# Sheet.net
KiCad netlist of a schematic drawn in Altium Designer
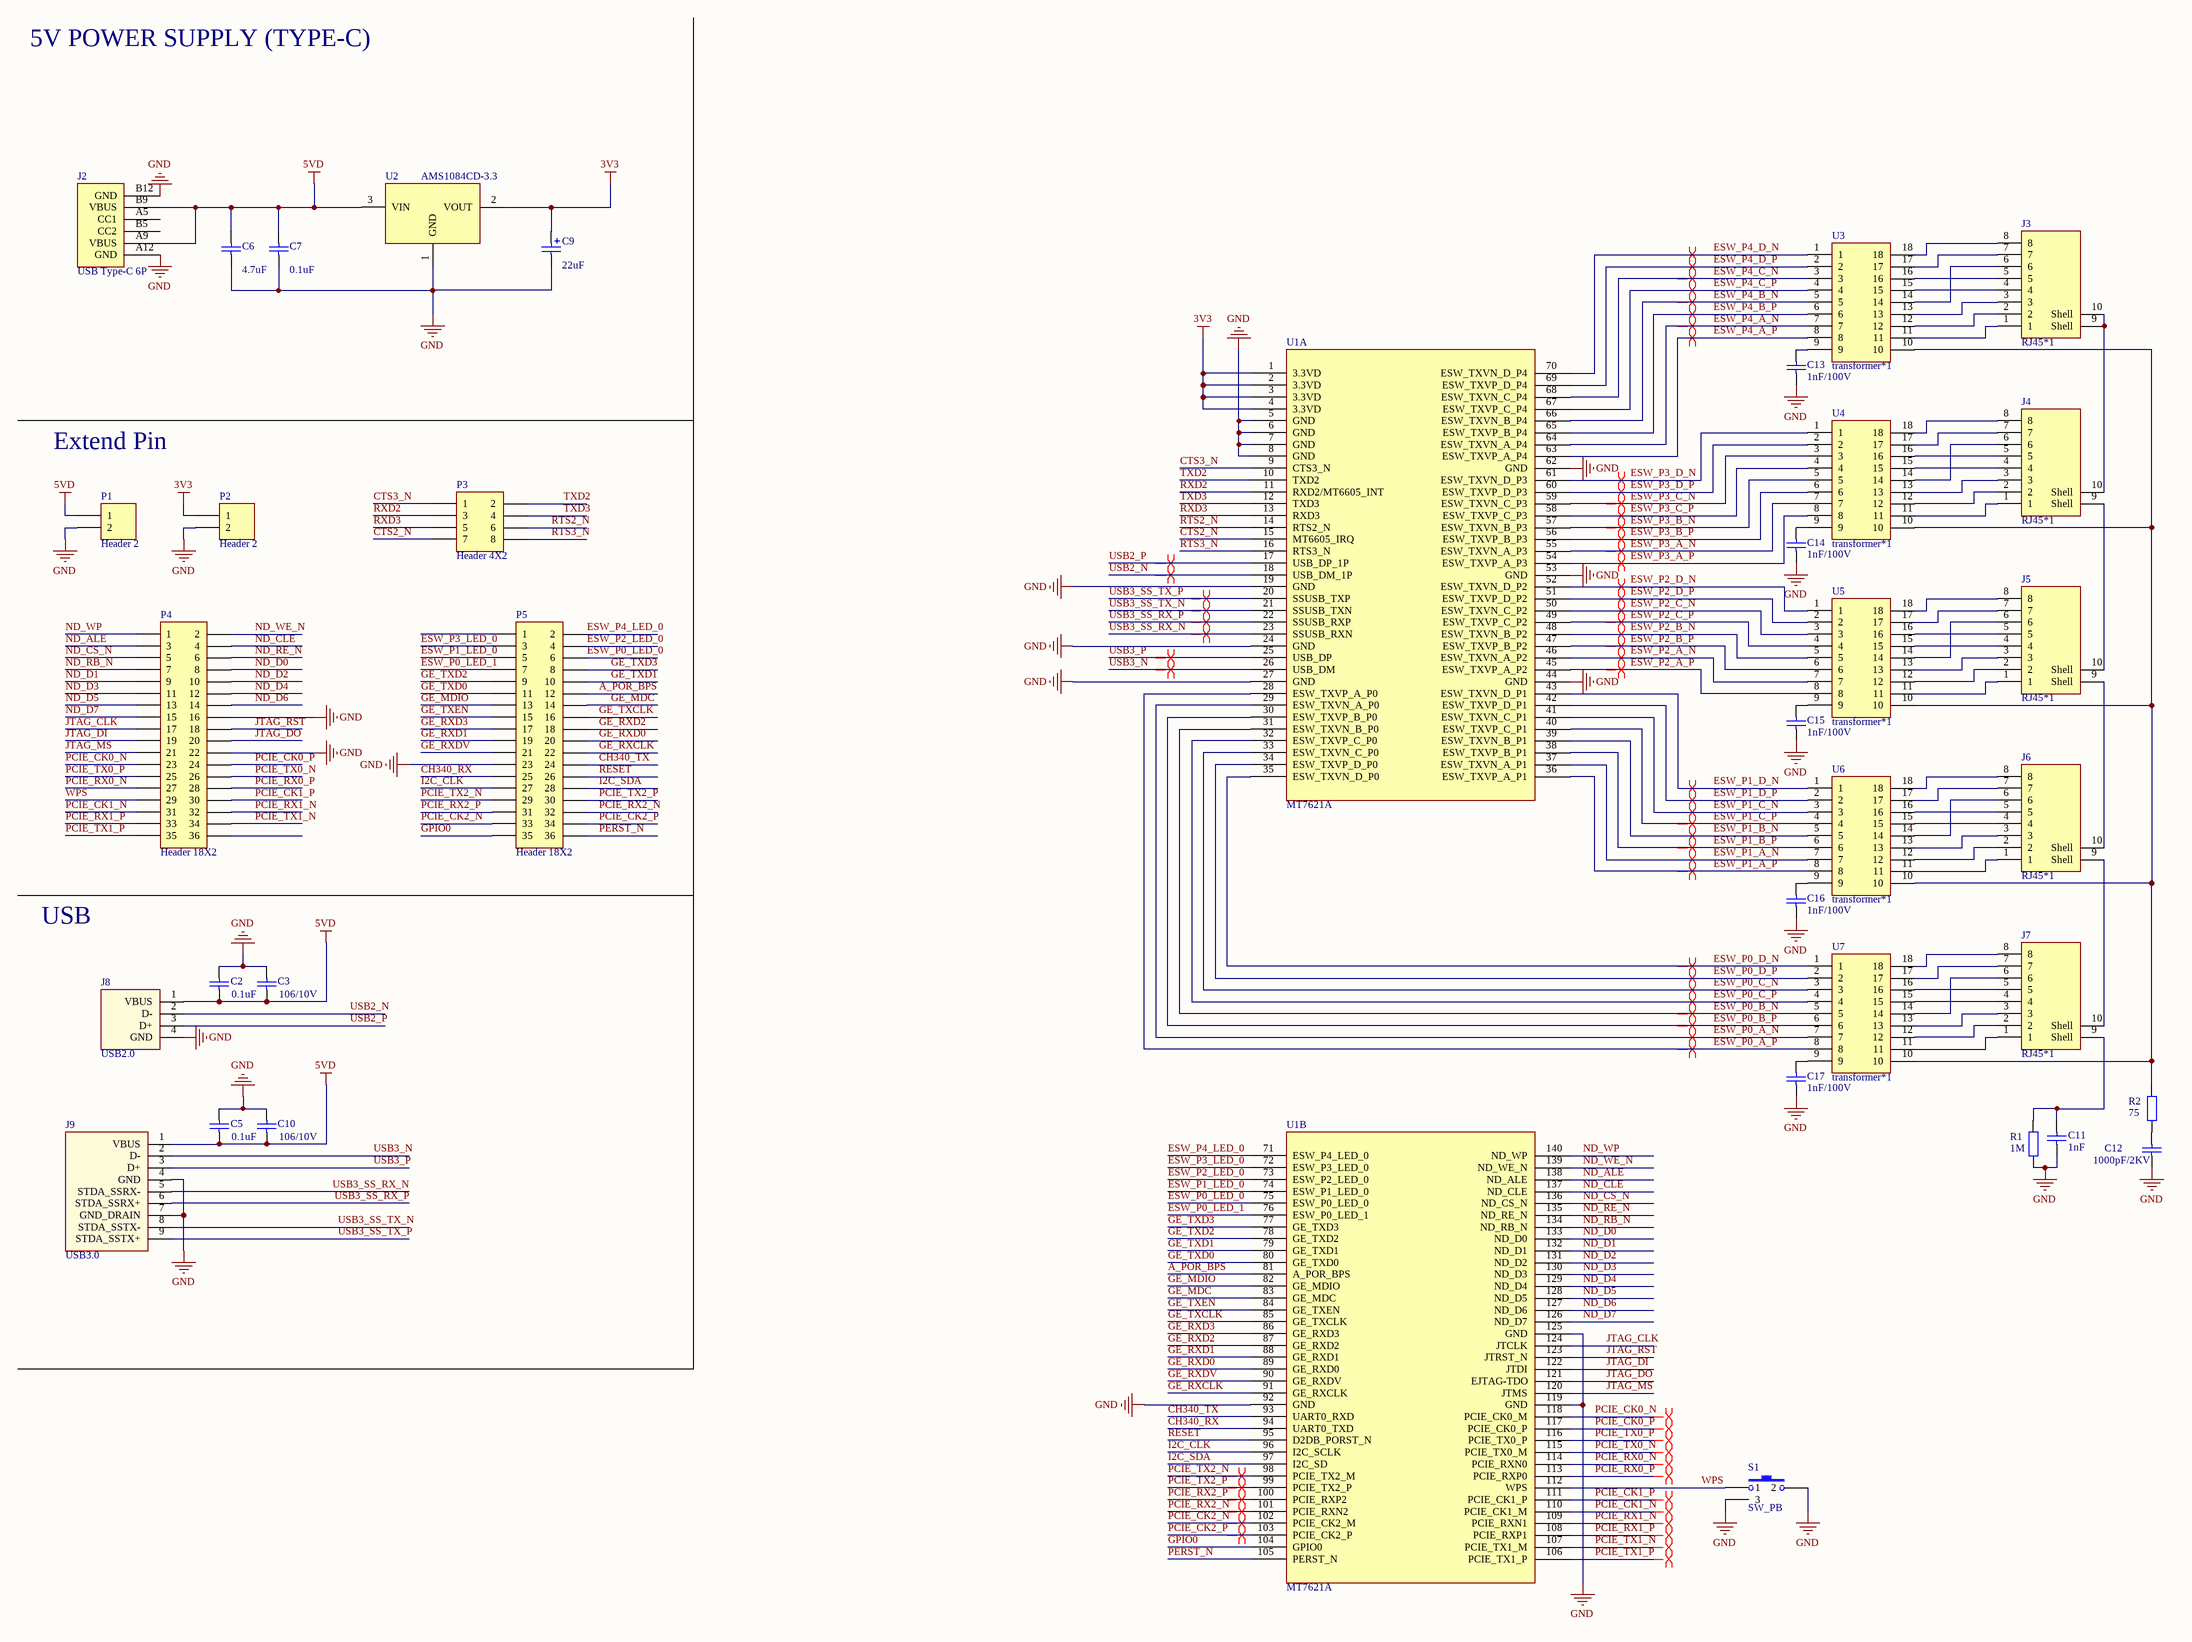
[diagram p0: Sheet.SchDoc]

(export (version "E")
  (design (tool "Eeschema 10.0.6"))
  (components
    (comp (ref "C2")
      (value "0.1uF")
      (footprint "6-0805")
      (description "Capacitor")
      (fields (field (name "Comment") "Cap") (field (name "PUBLISHER") "Altium Limited"))
      (libsource (lib "Miscellaneous Devices") (part "Cap"))
    )
    (comp (ref "C3")
      (value "106/10V")
      (footprint "6-0805")
      (description "Capacitor")
      (fields (field (name "Comment") "Cap") (field (name "PUBLISHER") "Altium Limited"))
      (libsource (lib "Miscellaneous Devices") (part "Cap"))
    )
    (comp (ref "C5")
      (value "0.1uF")
      (footprint "6-0805")
      (description "Capacitor")
      (fields (field (name "Comment") "Cap") (field (name "PUBLISHER") "Altium Limited"))
      (libsource (lib "Miscellaneous Devices") (part "Cap"))
    )
    (comp (ref "C6")
      (value "4.7uF")
      (footprint "6-0805")
      (description "Capacitor")
      (fields (field (name "Comment") "Cap") (field (name "PUBLISHER") "Altium Limited"))
      (libsource (lib "Miscellaneous Devices") (part "Cap"))
    )
    (comp (ref "C7")
      (value "0.1uF")
      (footprint "6-0805")
      (description "Capacitor")
      (fields (field (name "Comment") "Cap") (field (name "PUBLISHER") "Altium Limited"))
      (libsource (lib "Miscellaneous Devices") (part "Cap"))
    )
    (comp (ref "C9")
      (value "22uF")
      (footprint "3528B")
      (description "Polarized Capacitor (Axial)")
      (fields (field (name "Comment") "Cap Pol2") (field (name "PUBLISHER") "Altium Limited"))
      (libsource (lib "Miscellaneous Devices") (part "Cap Pol2"))
    )
    (comp (ref "C10")
      (value "106/10V")
      (footprint "6-0805")
      (description "Capacitor")
      (fields (field (name "Comment") "Cap") (field (name "PUBLISHER") "Altium Limited"))
      (libsource (lib "Miscellaneous Devices") (part "Cap"))
    )
    (comp (ref "C11")
      (value "1nF")
      (footprint "8-1206")
      (description "Capacitor")
      (fields (field (name "Comment") "Cap") (field (name "PUBLISHER") "Altium Limited"))
      (libsource (lib "Miscellaneous Devices") (part "Cap"))
    )
    (comp (ref "C12")
      (value "1000pF/2KV")
      (footprint "8-1206")
      (description "Capacitor")
      (fields (field (name "Comment") "Cap") (field (name "PUBLISHER") "Altium Limited"))
      (libsource (lib "Miscellaneous Devices") (part "Cap"))
    )
    (comp (ref "C13")
      (value "1nF/100V")
      (footprint "6-0805")
      (description "Capacitor")
      (fields (field (name "Comment") "Cap") (field (name "PUBLISHER") "Altium Limited"))
      (libsource (lib "Miscellaneous Devices") (part "Cap"))
    )
    (comp (ref "C14")
      (value "1nF/100V")
      (footprint "6-0805")
      (description "Capacitor")
      (fields (field (name "Comment") "Cap") (field (name "PUBLISHER") "Altium Limited"))
      (libsource (lib "Miscellaneous Devices") (part "Cap"))
    )
    (comp (ref "C15")
      (value "1nF/100V")
      (footprint "6-0805")
      (description "Capacitor")
      (fields (field (name "Comment") "Cap") (field (name "PUBLISHER") "Altium Limited"))
      (libsource (lib "Miscellaneous Devices") (part "Cap"))
    )
    (comp (ref "C16")
      (value "1nF/100V")
      (footprint "6-0805")
      (description "Capacitor")
      (fields (field (name "Comment") "Cap") (field (name "PUBLISHER") "Altium Limited"))
      (libsource (lib "Miscellaneous Devices") (part "Cap"))
    )
    (comp (ref "C17")
      (value "1nF/100V")
      (footprint "6-0805")
      (description "Capacitor")
      (fields (field (name "Comment") "Cap") (field (name "PUBLISHER") "Altium Limited"))
      (libsource (lib "Miscellaneous Devices") (part "Cap"))
    )
    (comp (ref "J2")
      (value "USB Type-C 6P")
      (footprint "USB Type-C 6P")
      (libsource (lib "7621_cmp") (part "USB Type-C 6P"))
    )
    (comp (ref "J3") (value "RJ45*1") (libsource (lib "7621_cmp") (part "RJ45*1")))
    (comp (ref "J4") (value "RJ45*1") (libsource (lib "7621_cmp") (part "RJ45*1")))
    (comp (ref "J5") (value "RJ45*1") (libsource (lib "7621_cmp") (part "RJ45*1")))
    (comp (ref "J6") (value "RJ45*1") (libsource (lib "7621_cmp") (part "RJ45*1")))
    (comp (ref "J7") (value "RJ45*1") (libsource (lib "7621_cmp") (part "RJ45*1")))
    (comp (ref "J8") (value "USB2.0") (footprint "USB2.0") (libsource (lib "7621_cmp") (part "USB2.0")))
    (comp (ref "J9") (value "USB3.0") (footprint "USB3.0_0") (libsource (lib "7621_cmp") (part "USB3.0")))
    (comp (ref "P1")
      (value "Header 2")
      (footprint "HDR1X2")
      (description "Header, 2-Pin")
      (fields (field (name "PUBLISHER") "Altium Limited"))
      (libsource (lib "Miscellaneous Connectors") (part "Header 2"))
    )
    (comp (ref "P2")
      (value "Header 2")
      (footprint "HDR1X2")
      (description "Header, 2-Pin")
      (fields (field (name "PUBLISHER") "Altium Limited"))
      (libsource (lib "Miscellaneous Connectors") (part "Header 2"))
    )
    (comp (ref "P3")
      (value "Header 4X2")
      (footprint "HDR2X4")
      (description "Header, 4-Pin, Dual row")
      (fields (field (name "PUBLISHER") "Altium Limited"))
      (libsource (lib "Miscellaneous Connectors") (part "Header 4X2"))
    )
    (comp (ref "P4")
      (value "Header 18X2")
      (footprint "HDR2X18")
      (description "Header, 18-Pin, Dual row")
      (fields (field (name "PUBLISHER") "Altium Limited"))
      (libsource (lib "Miscellaneous Connectors") (part "Header 18X2"))
    )
    (comp (ref "P5")
      (value "Header 18X2")
      (footprint "HDR2X18")
      (description "Header, 18-Pin, Dual row")
      (fields (field (name "PUBLISHER") "Altium Limited"))
      (libsource (lib "Miscellaneous Connectors") (part "Header 18X2"))
    )
    (comp (ref "R1")
      (value "1M")
      (footprint "8-1206")
      (description "Resistor")
      (fields (field (name "Comment") "Res2") (field (name "PUBLISHER") "Altium Limited"))
      (libsource (lib "Miscellaneous Devices") (part "Res2"))
    )
    (comp (ref "R2")
      (value "75")
      (footprint "8-1206")
      (description "Resistor")
      (fields (field (name "Comment") "Res2") (field (name "PUBLISHER") "Altium Limited"))
      (libsource (lib "Miscellaneous Devices") (part "Res2"))
    )
    (comp (ref "S1") (value "SW_PB") (footprint "SW_PB") (libsource (lib "7621_cmp") (part "SW_PB")))
    (comp (ref "U1") (value "MT7621A") (footprint "HLK-7621") (libsource (lib "7621_cmp") (part "MT7621A")))
    (comp (ref "U2")
      (value "AMS1084CD-3.3")
      (footprint "TO252")
      (libsource (lib "7621_cmp") (part "AMS1084CD-3.3"))
    )
    (comp (ref "U3")
      (value "transformer*1")
      (footprint "transformer_G1801D")
      (libsource (lib "7621_cmp") (part "transformer*1"))
    )
    (comp (ref "U4")
      (value "transformer*1")
      (footprint "transformer_G1801D")
      (libsource (lib "7621_cmp") (part "transformer*1"))
    )
    (comp (ref "U5")
      (value "transformer*1")
      (footprint "transformer_G1801D")
      (libsource (lib "7621_cmp") (part "transformer*1"))
    )
    (comp (ref "U6")
      (value "transformer*1")
      (footprint "transformer_G1801D")
      (libsource (lib "7621_cmp") (part "transformer*1"))
    )
    (comp (ref "U7")
      (value "transformer*1")
      (footprint "transformer_G1801D")
      (libsource (lib "7621_cmp") (part "transformer*1"))
    )
  )
  (nets
    (net (code "1") (name "/A_POR_BPS") (class "Default")
      (node (ref "P5") (pin "12") (pinfunction "12_12") (pintype "passive"))
      (node (ref "U1") (pin "81") (pinfunction "A_POR_BPS_81") (pintype "passive"))
    )
    (net (code "2") (name "/CH340_RX") (class "Default")
      (node (ref "P5") (pin "25") (pinfunction "25_25") (pintype "passive"))
      (node (ref "U1") (pin "94") (pinfunction "UART0_TXD_94") (pintype "passive"))
    )
    (net (code "3") (name "/CH340_TX") (class "Default")
      (node (ref "P5") (pin "24") (pinfunction "24_24") (pintype "passive"))
      (node (ref "U1") (pin "93") (pinfunction "UART0_RXD_93") (pintype "passive"))
    )
    (net (code "4") (name "/CTS2_N") (class "Default")
      (node (ref "P3") (pin "7") (pinfunction "7_7") (pintype "passive"))
      (node (ref "U1") (pin "15") (pinfunction "MT6605_IRQ_15") (pintype "passive"))
    )
    (net (code "5") (name "/CTS3_N") (class "Default")
      (node (ref "P3") (pin "1") (pinfunction "1_1") (pintype "passive"))
      (node (ref "U1") (pin "9") (pinfunction "CTS3_N_9") (pintype "passive"))
    )
    (net (code "6") (name "/ESW_P0_A_N") (class "Default")
      (node (ref "U1") (pin "29") (pinfunction "ESW_TXVN_A_P0_29") (pintype "passive"))
      (node (ref "U7") (pin "7") (pinfunction "7_7") (pintype "passive"))
    )
    (net (code "7") (name "/ESW_P0_A_P") (class "Default")
      (node (ref "U1") (pin "28") (pinfunction "ESW_TXVP_A_P0_28") (pintype "passive"))
      (node (ref "U7") (pin "8") (pinfunction "8_8") (pintype "passive"))
    )
    (net (code "8") (name "/ESW_P0_B_N") (class "Default")
      (node (ref "U1") (pin "31") (pinfunction "ESW_TXVN_B_P0_31") (pintype "passive"))
      (node (ref "U7") (pin "5") (pinfunction "5_5") (pintype "passive"))
    )
    (net (code "9") (name "/ESW_P0_B_P") (class "Default")
      (node (ref "U1") (pin "30") (pinfunction "ESW_TXVP_B_P0_30") (pintype "passive"))
      (node (ref "U7") (pin "6") (pinfunction "6_6") (pintype "passive"))
    )
    (net (code "10") (name "/ESW_P0_C_N") (class "Default")
      (node (ref "U1") (pin "33") (pinfunction "ESW_TXVN_C_P0_33") (pintype "passive"))
      (node (ref "U7") (pin "3") (pinfunction "3_3") (pintype "passive"))
    )
    (net (code "11") (name "/ESW_P0_C_P") (class "Default")
      (node (ref "U1") (pin "32") (pinfunction "ESW_TXVP_C_P0_32") (pintype "passive"))
      (node (ref "U7") (pin "4") (pinfunction "4_4") (pintype "passive"))
    )
    (net (code "12") (name "/ESW_P0_D_N") (class "Default")
      (node (ref "U1") (pin "35") (pinfunction "ESW_TXVN_D_P0_35") (pintype "passive"))
      (node (ref "U7") (pin "1") (pinfunction "1_1") (pintype "passive"))
    )
    (net (code "13") (name "/ESW_P0_D_P") (class "Default")
      (node (ref "U1") (pin "34") (pinfunction "ESW_TXVP_D_P0_34") (pintype "passive"))
      (node (ref "U7") (pin "2") (pinfunction "2_2") (pintype "passive"))
    )
    (net (code "14") (name "/ESW_P0_LED_0") (class "Default")
      (node (ref "P5") (pin "6") (pinfunction "6_6") (pintype "passive"))
      (node (ref "U1") (pin "75") (pinfunction "ESW_P0_LED_0_75") (pintype "passive"))
    )
    (net (code "15") (name "/ESW_P0_LED_1") (class "Default")
      (node (ref "P5") (pin "7") (pinfunction "7_7") (pintype "passive"))
      (node (ref "U1") (pin "76") (pinfunction "ESW_P0_LED_1_76") (pintype "passive"))
    )
    (net (code "16") (name "/ESW_P1_A_N") (class "Default")
      (node (ref "U1") (pin "37") (pinfunction "ESW_TXVN_A_P1_37") (pintype "passive"))
      (node (ref "U6") (pin "7") (pinfunction "7_7") (pintype "passive"))
    )
    (net (code "17") (name "/ESW_P1_A_P") (class "Default")
      (node (ref "U1") (pin "36") (pinfunction "ESW_TXVP_A_P1_36") (pintype "passive"))
      (node (ref "U6") (pin "8") (pinfunction "8_8") (pintype "passive"))
    )
    (net (code "18") (name "/ESW_P1_B_N") (class "Default")
      (node (ref "U1") (pin "39") (pinfunction "ESW_TXVN_B_P1_39") (pintype "passive"))
      (node (ref "U6") (pin "5") (pinfunction "5_5") (pintype "passive"))
    )
    (net (code "19") (name "/ESW_P1_B_P") (class "Default")
      (node (ref "U1") (pin "38") (pinfunction "ESW_TXVP_B_P1_38") (pintype "passive"))
      (node (ref "U6") (pin "6") (pinfunction "6_6") (pintype "passive"))
    )
    (net (code "20") (name "/ESW_P1_C_N") (class "Default")
      (node (ref "U1") (pin "41") (pinfunction "ESW_TXVN_C_P1_41") (pintype "passive"))
      (node (ref "U6") (pin "3") (pinfunction "3_3") (pintype "passive"))
    )
    (net (code "21") (name "/ESW_P1_C_P") (class "Default")
      (node (ref "U1") (pin "40") (pinfunction "ESW_TXVP_C_P1_40") (pintype "passive"))
      (node (ref "U6") (pin "4") (pinfunction "4_4") (pintype "passive"))
    )
    (net (code "22") (name "/ESW_P1_D_N") (class "Default")
      (node (ref "U1") (pin "43") (pinfunction "ESW_TXVN_D_P1_43") (pintype "passive"))
      (node (ref "U6") (pin "1") (pinfunction "1_1") (pintype "passive"))
    )
    (net (code "23") (name "/ESW_P1_D_P") (class "Default")
      (node (ref "U1") (pin "42") (pinfunction "ESW_TXVP_D_P1_42") (pintype "passive"))
      (node (ref "U6") (pin "2") (pinfunction "2_2") (pintype "passive"))
    )
    (net (code "24") (name "/ESW_P1_LED_0") (class "Default")
      (node (ref "P5") (pin "5") (pinfunction "5_5") (pintype "passive"))
      (node (ref "U1") (pin "74") (pinfunction "ESW_P1_LED_0_74") (pintype "passive"))
    )
    (net (code "25") (name "/ESW_P2_A_N") (class "Default")
      (node (ref "U1") (pin "46") (pinfunction "ESW_TXVN_A_P2_46") (pintype "passive"))
      (node (ref "U5") (pin "7") (pinfunction "7_7") (pintype "passive"))
    )
    (net (code "26") (name "/ESW_P2_A_P") (class "Default")
      (node (ref "U1") (pin "45") (pinfunction "ESW_TXVP_A_P2_45") (pintype "passive"))
      (node (ref "U5") (pin "8") (pinfunction "8_8") (pintype "passive"))
    )
    (net (code "27") (name "/ESW_P2_B_N") (class "Default")
      (node (ref "U1") (pin "48") (pinfunction "ESW_TXVN_B_P2_48") (pintype "passive"))
      (node (ref "U5") (pin "5") (pinfunction "5_5") (pintype "passive"))
    )
    (net (code "28") (name "/ESW_P2_B_P") (class "Default")
      (node (ref "U1") (pin "47") (pinfunction "ESW_TXVP_B_P2_47") (pintype "passive"))
      (node (ref "U5") (pin "6") (pinfunction "6_6") (pintype "passive"))
    )
    (net (code "29") (name "/ESW_P2_C_N") (class "Default")
      (node (ref "U1") (pin "50") (pinfunction "ESW_TXVN_C_P2_50") (pintype "passive"))
      (node (ref "U5") (pin "3") (pinfunction "3_3") (pintype "passive"))
    )
    (net (code "30") (name "/ESW_P2_C_P") (class "Default")
      (node (ref "U1") (pin "49") (pinfunction "ESW_TXVP_C_P2_49") (pintype "passive"))
      (node (ref "U5") (pin "4") (pinfunction "4_4") (pintype "passive"))
    )
    (net (code "31") (name "/ESW_P2_D_N") (class "Default")
      (node (ref "U1") (pin "52") (pinfunction "ESW_TXVN_D_P2_52") (pintype "passive"))
      (node (ref "U5") (pin "1") (pinfunction "1_1") (pintype "passive"))
    )
    (net (code "32") (name "/ESW_P2_D_P") (class "Default")
      (node (ref "U1") (pin "51") (pinfunction "ESW_TXVP_D_P2_51") (pintype "passive"))
      (node (ref "U5") (pin "2") (pinfunction "2_2") (pintype "passive"))
    )
    (net (code "33") (name "/ESW_P2_LED_0") (class "Default")
      (node (ref "P5") (pin "4") (pinfunction "4_4") (pintype "passive"))
      (node (ref "U1") (pin "73") (pinfunction "ESW_P2_LED_0_73") (pintype "passive"))
    )
    (net (code "34") (name "/ESW_P3_A_N") (class "Default")
      (node (ref "U1") (pin "55") (pinfunction "ESW_TXVN_A_P3_55") (pintype "passive"))
      (node (ref "U4") (pin "7") (pinfunction "7_7") (pintype "passive"))
    )
    (net (code "35") (name "/ESW_P3_A_P") (class "Default")
      (node (ref "U1") (pin "54") (pinfunction "ESW_TXVP_A_P3_54") (pintype "passive"))
      (node (ref "U4") (pin "8") (pinfunction "8_8") (pintype "passive"))
    )
    (net (code "36") (name "/ESW_P3_B_N") (class "Default")
      (node (ref "U1") (pin "57") (pinfunction "ESW_TXVN_B_P3_57") (pintype "passive"))
      (node (ref "U4") (pin "5") (pinfunction "5_5") (pintype "passive"))
    )
    (net (code "37") (name "/ESW_P3_B_P") (class "Default")
      (node (ref "U1") (pin "56") (pinfunction "ESW_TXVP_B_P3_56") (pintype "passive"))
      (node (ref "U4") (pin "6") (pinfunction "6_6") (pintype "passive"))
    )
    (net (code "38") (name "/ESW_P3_C_N") (class "Default")
      (node (ref "U1") (pin "59") (pinfunction "ESW_TXVN_C_P3_59") (pintype "passive"))
      (node (ref "U4") (pin "3") (pinfunction "3_3") (pintype "passive"))
    )
    (net (code "39") (name "/ESW_P3_C_P") (class "Default")
      (node (ref "U1") (pin "58") (pinfunction "ESW_TXVP_C_P3_58") (pintype "passive"))
      (node (ref "U4") (pin "4") (pinfunction "4_4") (pintype "passive"))
    )
    (net (code "40") (name "/ESW_P3_D_N") (class "Default")
      (node (ref "U1") (pin "61") (pinfunction "ESW_TXVN_D_P3_61") (pintype "passive"))
      (node (ref "U4") (pin "1") (pinfunction "1_1") (pintype "passive"))
    )
    (net (code "41") (name "/ESW_P3_D_P") (class "Default")
      (node (ref "U1") (pin "60") (pinfunction "ESW_TXVP_D_P3_60") (pintype "passive"))
      (node (ref "U4") (pin "2") (pinfunction "2_2") (pintype "passive"))
    )
    (net (code "42") (name "/ESW_P3_LED_0") (class "Default")
      (node (ref "P5") (pin "3") (pinfunction "3_3") (pintype "passive"))
      (node (ref "U1") (pin "72") (pinfunction "ESW_P3_LED_0_72") (pintype "passive"))
    )
    (net (code "43") (name "/ESW_P4_A_N") (class "Default")
      (node (ref "U1") (pin "64") (pinfunction "ESW_TXVN_A_P4_64") (pintype "passive"))
      (node (ref "U3") (pin "7") (pinfunction "7_7") (pintype "passive"))
    )
    (net (code "44") (name "/ESW_P4_A_P") (class "Default")
      (node (ref "U1") (pin "63") (pinfunction "ESW_TXVP_A_P4_63") (pintype "passive"))
      (node (ref "U3") (pin "8") (pinfunction "8_8") (pintype "passive"))
    )
    (net (code "45") (name "/ESW_P4_B_N") (class "Default")
      (node (ref "U1") (pin "66") (pinfunction "ESW_TXVN_B_P4_66") (pintype "passive"))
      (node (ref "U3") (pin "5") (pinfunction "5_5") (pintype "passive"))
    )
    (net (code "46") (name "/ESW_P4_B_P") (class "Default")
      (node (ref "U1") (pin "65") (pinfunction "ESW_TXVP_B_P4_65") (pintype "passive"))
      (node (ref "U3") (pin "6") (pinfunction "6_6") (pintype "passive"))
    )
    (net (code "47") (name "/ESW_P4_C_N") (class "Default")
      (node (ref "U1") (pin "68") (pinfunction "ESW_TXVN_C_P4_68") (pintype "passive"))
      (node (ref "U3") (pin "3") (pinfunction "3_3") (pintype "passive"))
    )
    (net (code "48") (name "/ESW_P4_C_P") (class "Default")
      (node (ref "U1") (pin "67") (pinfunction "ESW_TXVP_C_P4_67") (pintype "passive"))
      (node (ref "U3") (pin "4") (pinfunction "4_4") (pintype "passive"))
    )
    (net (code "49") (name "/ESW_P4_D_N") (class "Default")
      (node (ref "U1") (pin "70") (pinfunction "ESW_TXVN_D_P4_70") (pintype "passive"))
      (node (ref "U3") (pin "1") (pinfunction "1_1") (pintype "passive"))
    )
    (net (code "50") (name "/ESW_P4_D_P") (class "Default")
      (node (ref "U1") (pin "69") (pinfunction "ESW_TXVP_D_P4_69") (pintype "passive"))
      (node (ref "U3") (pin "2") (pinfunction "2_2") (pintype "passive"))
    )
    (net (code "51") (name "/ESW_P4_LED_0") (class "Default")
      (node (ref "P5") (pin "2") (pinfunction "2_2") (pintype "passive"))
      (node (ref "U1") (pin "71") (pinfunction "ESW_P4_LED_0_71") (pintype "passive"))
    )
    (net (code "52") (name "/GE_MDC") (class "Default")
      (node (ref "P5") (pin "14") (pinfunction "14_14") (pintype "passive"))
      (node (ref "U1") (pin "83") (pinfunction "GE_MDC_83") (pintype "passive"))
    )
    (net (code "53") (name "/GE_MDIO") (class "Default")
      (node (ref "P5") (pin "13") (pinfunction "13_13") (pintype "passive"))
      (node (ref "U1") (pin "82") (pinfunction "GE_MDIO_82") (pintype "passive"))
    )
    (net (code "54") (name "/GE_RXCLK") (class "Default")
      (node (ref "P5") (pin "22") (pinfunction "22_22") (pintype "passive"))
      (node (ref "U1") (pin "91") (pinfunction "GE_RXCLK_91") (pintype "passive"))
    )
    (net (code "55") (name "/GE_RXD0") (class "Default")
      (node (ref "P5") (pin "20") (pinfunction "20_20") (pintype "passive"))
      (node (ref "U1") (pin "89") (pinfunction "GE_RXD0_89") (pintype "passive"))
    )
    (net (code "56") (name "/GE_RXD1") (class "Default")
      (node (ref "P5") (pin "19") (pinfunction "19_19") (pintype "passive"))
      (node (ref "U1") (pin "88") (pinfunction "GE_RXD1_88") (pintype "passive"))
    )
    (net (code "57") (name "/GE_RXD2") (class "Default")
      (node (ref "P5") (pin "18") (pinfunction "18_18") (pintype "passive"))
      (node (ref "U1") (pin "87") (pinfunction "GE_RXD2_87") (pintype "passive"))
    )
    (net (code "58") (name "/GE_RXD3") (class "Default")
      (node (ref "P5") (pin "17") (pinfunction "17_17") (pintype "passive"))
      (node (ref "U1") (pin "86") (pinfunction "GE_RXD3_86") (pintype "passive"))
    )
    (net (code "59") (name "/GE_RXDV") (class "Default")
      (node (ref "P5") (pin "21") (pinfunction "21_21") (pintype "passive"))
      (node (ref "U1") (pin "90") (pinfunction "GE_RXDV_90") (pintype "passive"))
    )
    (net (code "60") (name "/GE_TXCLK") (class "Default")
      (node (ref "P5") (pin "16") (pinfunction "16_16") (pintype "passive"))
      (node (ref "U1") (pin "85") (pinfunction "GE_TXCLK_85") (pintype "passive"))
    )
    (net (code "61") (name "/GE_TXD0") (class "Default")
      (node (ref "P5") (pin "11") (pinfunction "11_11") (pintype "passive"))
      (node (ref "U1") (pin "80") (pinfunction "GE_TXD0_80") (pintype "passive"))
    )
    (net (code "62") (name "/GE_TXD1") (class "Default")
      (node (ref "P5") (pin "10") (pinfunction "10_10") (pintype "passive"))
      (node (ref "U1") (pin "79") (pinfunction "GE_TXD1_79") (pintype "passive"))
    )
    (net (code "63") (name "/GE_TXD2") (class "Default")
      (node (ref "P5") (pin "9") (pinfunction "9_9") (pintype "passive"))
      (node (ref "U1") (pin "78") (pinfunction "GE_TXD2_78") (pintype "passive"))
    )
    (net (code "64") (name "/GE_TXD3") (class "Default")
      (node (ref "P5") (pin "8") (pinfunction "8_8") (pintype "passive"))
      (node (ref "U1") (pin "77") (pinfunction "GE_TXD3_77") (pintype "passive"))
    )
    (net (code "65") (name "/GE_TXEN") (class "Default")
      (node (ref "P5") (pin "15") (pinfunction "15_15") (pintype "passive"))
      (node (ref "U1") (pin "84") (pinfunction "GE_TXEN_84") (pintype "passive"))
    )
    (net (code "66") (name "/GPIO0") (class "Default")
      (node (ref "P5") (pin "35") (pinfunction "35_35") (pintype "passive"))
      (node (ref "U1") (pin "104") (pinfunction "GPIO0_104") (pintype "passive"))
    )
    (net (code "67") (name "/I2C_CLK") (class "Default")
      (node (ref "P5") (pin "27") (pinfunction "27_27") (pintype "passive"))
      (node (ref "U1") (pin "96") (pinfunction "I2C_SCLK_96") (pintype "passive"))
    )
    (net (code "68") (name "/I2C_SDA") (class "Default")
      (node (ref "P5") (pin "28") (pinfunction "28_28") (pintype "passive"))
      (node (ref "U1") (pin "97") (pinfunction "I2C_SD_97") (pintype "passive"))
    )
    (net (code "69") (name "/JTAG_CLK") (class "Default")
      (node (ref "P4") (pin "17") (pinfunction "17_17") (pintype "passive"))
      (node (ref "U1") (pin "124") (pinfunction "JTCLK_124") (pintype "passive"))
    )
    (net (code "70") (name "/JTAG_DI") (class "Default")
      (node (ref "P4") (pin "19") (pinfunction "19_19") (pintype "passive"))
      (node (ref "U1") (pin "122") (pinfunction "JTDI_122") (pintype "passive"))
    )
    (net (code "71") (name "/JTAG_DO") (class "Default")
      (node (ref "P4") (pin "20") (pinfunction "20_20") (pintype "passive"))
      (node (ref "U1") (pin "121") (pinfunction "EJTAG-TDO_121") (pintype "passive"))
    )
    (net (code "72") (name "/JTAG_MS") (class "Default")
      (node (ref "P4") (pin "21") (pinfunction "21_21") (pintype "passive"))
      (node (ref "U1") (pin "120") (pinfunction "JTMS_120") (pintype "passive"))
    )
    (net (code "73") (name "/JTAG_RST") (class "Default")
      (node (ref "P4") (pin "18") (pinfunction "18_18") (pintype "passive"))
      (node (ref "U1") (pin "123") (pinfunction "JTRST_N_123") (pintype "passive"))
    )
    (net (code "74") (name "/ND_ALE") (class "Default")
      (node (ref "P4") (pin "3") (pinfunction "3_3") (pintype "passive"))
      (node (ref "U1") (pin "138") (pinfunction "ND_ALE_138") (pintype "passive"))
    )
    (net (code "75") (name "/ND_CLE") (class "Default")
      (node (ref "P4") (pin "4") (pinfunction "4_4") (pintype "passive"))
      (node (ref "U1") (pin "137") (pinfunction "ND_CLE_137") (pintype "passive"))
    )
    (net (code "76") (name "/ND_CS_N") (class "Default")
      (node (ref "P4") (pin "5") (pinfunction "5_5") (pintype "passive"))
      (node (ref "U1") (pin "136") (pinfunction "ND_CS_N_136") (pintype "passive"))
    )
    (net (code "77") (name "/ND_D0") (class "Default")
      (node (ref "P4") (pin "8") (pinfunction "8_8") (pintype "passive"))
      (node (ref "U1") (pin "133") (pinfunction "ND_D0_133") (pintype "passive"))
    )
    (net (code "78") (name "/ND_D1") (class "Default")
      (node (ref "P4") (pin "9") (pinfunction "9_9") (pintype "passive"))
      (node (ref "U1") (pin "132") (pinfunction "ND_D1_132") (pintype "passive"))
    )
    (net (code "79") (name "/ND_D2") (class "Default")
      (node (ref "P4") (pin "10") (pinfunction "10_10") (pintype "passive"))
      (node (ref "U1") (pin "131") (pinfunction "ND_D2_131") (pintype "passive"))
    )
    (net (code "80") (name "/ND_D3") (class "Default")
      (node (ref "P4") (pin "11") (pinfunction "11_11") (pintype "passive"))
      (node (ref "U1") (pin "130") (pinfunction "ND_D3_130") (pintype "passive"))
    )
    (net (code "81") (name "/ND_D4") (class "Default")
      (node (ref "P4") (pin "12") (pinfunction "12_12") (pintype "passive"))
      (node (ref "U1") (pin "129") (pinfunction "ND_D4_129") (pintype "passive"))
    )
    (net (code "82") (name "/ND_D5") (class "Default")
      (node (ref "P4") (pin "13") (pinfunction "13_13") (pintype "passive"))
      (node (ref "U1") (pin "128") (pinfunction "ND_D5_128") (pintype "passive"))
    )
    (net (code "83") (name "/ND_D6") (class "Default")
      (node (ref "P4") (pin "14") (pinfunction "14_14") (pintype "passive"))
      (node (ref "U1") (pin "127") (pinfunction "ND_D6_127") (pintype "passive"))
    )
    (net (code "84") (name "/ND_D7") (class "Default")
      (node (ref "P4") (pin "15") (pinfunction "15_15") (pintype "passive"))
      (node (ref "U1") (pin "126") (pinfunction "ND_D7_126") (pintype "passive"))
    )
    (net (code "85") (name "/ND_RB_N") (class "Default")
      (node (ref "P4") (pin "7") (pinfunction "7_7") (pintype "passive"))
      (node (ref "U1") (pin "134") (pinfunction "ND_RB_N_134") (pintype "passive"))
    )
    (net (code "86") (name "/ND_RE_N") (class "Default")
      (node (ref "P4") (pin "6") (pinfunction "6_6") (pintype "passive"))
      (node (ref "U1") (pin "135") (pinfunction "ND_RE_N_135") (pintype "passive"))
    )
    (net (code "87") (name "/ND_WE_N") (class "Default")
      (node (ref "P4") (pin "2") (pinfunction "2_2") (pintype "passive"))
      (node (ref "U1") (pin "139") (pinfunction "ND_WE_N_139") (pintype "passive"))
    )
    (net (code "88") (name "/ND_WP") (class "Default")
      (node (ref "P4") (pin "1") (pinfunction "1_1") (pintype "passive"))
      (node (ref "U1") (pin "140") (pinfunction "ND_WP_140") (pintype "passive"))
    )
    (net (code "89") (name "/PCIE_CK0_N") (class "Default")
      (node (ref "P4") (pin "23") (pinfunction "23_23") (pintype "passive"))
      (node (ref "U1") (pin "118") (pinfunction "PCIE_CK0_M_118") (pintype "passive"))
    )
    (net (code "90") (name "/PCIE_CK0_P") (class "Default")
      (node (ref "P4") (pin "24") (pinfunction "24_24") (pintype "passive"))
      (node (ref "U1") (pin "117") (pinfunction "PCIE_CK0_P_117") (pintype "passive"))
    )
    (net (code "91") (name "/PCIE_CK1_N") (class "Default")
      (node (ref "P4") (pin "31") (pinfunction "31_31") (pintype "passive"))
      (node (ref "U1") (pin "110") (pinfunction "PCIE_CK1_M_110") (pintype "passive"))
    )
    (net (code "92") (name "/PCIE_CK1_P") (class "Default")
      (node (ref "P4") (pin "30") (pinfunction "30_30") (pintype "passive"))
      (node (ref "U1") (pin "111") (pinfunction "PCIE_CK1_P_111") (pintype "passive"))
    )
    (net (code "93") (name "/PCIE_CK2_N") (class "Default")
      (node (ref "P5") (pin "33") (pinfunction "33_33") (pintype "passive"))
      (node (ref "U1") (pin "102") (pinfunction "PCIE_CK2_M_102") (pintype "passive"))
    )
    (net (code "94") (name "/PCIE_CK2_P") (class "Default")
      (node (ref "P5") (pin "34") (pinfunction "34_34") (pintype "passive"))
      (node (ref "U1") (pin "103") (pinfunction "PCIE_CK2_P_103") (pintype "passive"))
    )
    (net (code "95") (name "/PCIE_RX0_N") (class "Default")
      (node (ref "P4") (pin "27") (pinfunction "27_27") (pintype "passive"))
      (node (ref "U1") (pin "114") (pinfunction "PCIE_RXN0_114") (pintype "passive"))
    )
    (net (code "96") (name "/PCIE_RX0_P") (class "Default")
      (node (ref "P4") (pin "28") (pinfunction "28_28") (pintype "passive"))
      (node (ref "U1") (pin "113") (pinfunction "PCIE_RXP0_113") (pintype "passive"))
    )
    (net (code "97") (name "/PCIE_RX1_N") (class "Default")
      (node (ref "P4") (pin "32") (pinfunction "32_32") (pintype "passive"))
      (node (ref "U1") (pin "109") (pinfunction "PCIE_RXN1_109") (pintype "passive"))
    )
    (net (code "98") (name "/PCIE_RX1_P") (class "Default")
      (node (ref "P4") (pin "33") (pinfunction "33_33") (pintype "passive"))
      (node (ref "U1") (pin "108") (pinfunction "PCIE_RXP1_108") (pintype "passive"))
    )
    (net (code "99") (name "/PCIE_RX2_N") (class "Default")
      (node (ref "P5") (pin "32") (pinfunction "32_32") (pintype "passive"))
      (node (ref "U1") (pin "101") (pinfunction "PCIE_RXN2_101") (pintype "passive"))
    )
    (net (code "100") (name "/PCIE_RX2_P") (class "Default")
      (node (ref "P5") (pin "31") (pinfunction "31_31") (pintype "passive"))
      (node (ref "U1") (pin "100") (pinfunction "PCIE_RXP2_100") (pintype "passive"))
    )
    (net (code "101") (name "/PCIE_TX0_N") (class "Default")
      (node (ref "P4") (pin "26") (pinfunction "26_26") (pintype "passive"))
      (node (ref "U1") (pin "115") (pinfunction "PCIE_TX0_M_115") (pintype "passive"))
    )
    (net (code "102") (name "/PCIE_TX0_P") (class "Default")
      (node (ref "P4") (pin "25") (pinfunction "25_25") (pintype "passive"))
      (node (ref "U1") (pin "116") (pinfunction "PCIE_TX0_P_116") (pintype "passive"))
    )
    (net (code "103") (name "/PCIE_TX1_N") (class "Default")
      (node (ref "P4") (pin "34") (pinfunction "34_34") (pintype "passive"))
      (node (ref "U1") (pin "107") (pinfunction "PCIE_TX1_M_107") (pintype "passive"))
    )
    (net (code "104") (name "/PCIE_TX1_P") (class "Default")
      (node (ref "P4") (pin "35") (pinfunction "35_35") (pintype "passive"))
      (node (ref "U1") (pin "106") (pinfunction "PCIE_TX1_P_106") (pintype "passive"))
    )
    (net (code "105") (name "/PCIE_TX2_N") (class "Default")
      (node (ref "P5") (pin "29") (pinfunction "29_29") (pintype "passive"))
      (node (ref "U1") (pin "98") (pinfunction "PCIE_TX2_M_98") (pintype "passive"))
    )
    (net (code "106") (name "/PCIE_TX2_P") (class "Default")
      (node (ref "P5") (pin "30") (pinfunction "30_30") (pintype "passive"))
      (node (ref "U1") (pin "99") (pinfunction "PCIE_TX2_P_99") (pintype "passive"))
    )
    (net (code "107") (name "/PERST_N") (class "Default")
      (node (ref "P5") (pin "36") (pinfunction "36_36") (pintype "passive"))
      (node (ref "U1") (pin "105") (pinfunction "PERST_N_105") (pintype "passive"))
    )
    (net (code "108") (name "/RESET") (class "Default")
      (node (ref "P5") (pin "26") (pinfunction "26_26") (pintype "passive"))
      (node (ref "U1") (pin "95") (pinfunction "D2DB_PORST_N_95") (pintype "passive"))
    )
    (net (code "109") (name "/RTS2_N") (class "Default")
      (node (ref "P3") (pin "6") (pinfunction "6_6") (pintype "passive"))
      (node (ref "U1") (pin "14") (pinfunction "RTS2_N_14") (pintype "passive"))
    )
    (net (code "110") (name "/RTS3_N") (class "Default")
      (node (ref "P3") (pin "8") (pinfunction "8_8") (pintype "passive"))
      (node (ref "U1") (pin "16") (pinfunction "RTS3_N_16") (pintype "passive"))
    )
    (net (code "111") (name "/RXD2") (class "Default")
      (node (ref "P3") (pin "3") (pinfunction "3_3") (pintype "passive"))
      (node (ref "U1") (pin "11") (pinfunction "RXD2/MT6605_INT_11") (pintype "passive"))
    )
    (net (code "112") (name "/RXD3") (class "Default")
      (node (ref "P3") (pin "5") (pinfunction "5_5") (pintype "passive"))
      (node (ref "U1") (pin "13") (pinfunction "RXD3_13") (pintype "passive"))
    )
    (net (code "113") (name "/TXD2") (class "Default")
      (node (ref "P3") (pin "2") (pinfunction "2_2") (pintype "passive"))
      (node (ref "U1") (pin "10") (pinfunction "TXD2_10") (pintype "passive"))
    )
    (net (code "114") (name "/TXD3") (class "Default")
      (node (ref "P3") (pin "4") (pinfunction "4_4") (pintype "passive"))
      (node (ref "U1") (pin "12") (pinfunction "TXD3_12") (pintype "passive"))
    )
    (net (code "115") (name "/USB2_N") (class "Default")
      (node (ref "J8") (pin "2") (pinfunction "D-_2") (pintype "passive"))
      (node (ref "U1") (pin "18") (pinfunction "USB_DM_1P_18") (pintype "passive"))
    )
    (net (code "116") (name "/USB2_P") (class "Default")
      (node (ref "J8") (pin "3") (pinfunction "D+_3") (pintype "passive"))
      (node (ref "U1") (pin "17") (pinfunction "USB_DP_1P_17") (pintype "passive"))
    )
    (net (code "117") (name "/USB3_N") (class "Default")
      (node (ref "J9") (pin "2") (pinfunction "D-_2") (pintype "passive"))
      (node (ref "U1") (pin "26") (pinfunction "USB_DM_26") (pintype "passive"))
    )
    (net (code "118") (name "/USB3_P") (class "Default")
      (node (ref "J9") (pin "3") (pinfunction "D+_3") (pintype "passive"))
      (node (ref "U1") (pin "25") (pinfunction "USB_DP_25") (pintype "passive"))
    )
    (net (code "119") (name "/USB3_SS_RX_N") (class "Default")
      (node (ref "J9") (pin "5") (pinfunction "STDA_SSRX-_5") (pintype "passive"))
      (node (ref "U1") (pin "23") (pinfunction "SSUSB_RXN_23") (pintype "passive"))
    )
    (net (code "120") (name "/USB3_SS_RX_P") (class "Default")
      (node (ref "J9") (pin "6") (pinfunction "STDA_SSRX+_6") (pintype "passive"))
      (node (ref "U1") (pin "22") (pinfunction "SSUSB_RXP_22") (pintype "passive"))
    )
    (net (code "121") (name "/USB3_SS_TX_N") (class "Default")
      (node (ref "J9") (pin "8") (pinfunction "STDA_SSTX-_8") (pintype "passive"))
      (node (ref "U1") (pin "21") (pinfunction "SSUSB_TXN_21") (pintype "passive"))
    )
    (net (code "122") (name "/USB3_SS_TX_P") (class "Default")
      (node (ref "J9") (pin "9") (pinfunction "STDA_SSTX+_9") (pintype "passive"))
      (node (ref "U1") (pin "20") (pinfunction "SSUSB_TXP_20") (pintype "passive"))
    )
    (net (code "123") (name "/WPS") (class "Default")
      (node (ref "P4") (pin "29") (pinfunction "29_29") (pintype "passive"))
      (node (ref "S1") (pin "1") (pinfunction "1_1") (pintype "passive"))
      (node (ref "U1") (pin "112") (pinfunction "WPS_112") (pintype "passive"))
    )
    (net (code "124") (name "3V3") (class "Default")
      (node (ref "C9") (pin "1") (pinfunction "1_1") (pintype "passive"))
      (node (ref "P2") (pin "1") (pinfunction "1_1") (pintype "passive"))
      (node (ref "U1") (pin "1") (pinfunction "3.3VD_1") (pintype "passive"))
      (node (ref "U1") (pin "2") (pinfunction "3.3VD_2") (pintype "passive"))
      (node (ref "U1") (pin "3") (pinfunction "3.3VD_3") (pintype "passive"))
      (node (ref "U1") (pin "4") (pinfunction "3.3VD_4") (pintype "passive"))
      (node (ref "U2") (pin "2") (pinfunction "VOUT_2") (pintype "passive"))
    )
    (net (code "125") (name "5VD") (class "Default")
      (node (ref "C10") (pin "1") (pinfunction "1_1") (pintype "passive"))
      (node (ref "C2") (pin "1") (pinfunction "1_1") (pintype "passive"))
      (node (ref "C3") (pin "1") (pinfunction "1_1") (pintype "passive"))
      (node (ref "C5") (pin "1") (pinfunction "1_1") (pintype "passive"))
      (node (ref "C6") (pin "2") (pinfunction "2_2") (pintype "passive"))
      (node (ref "C7") (pin "2") (pinfunction "2_2") (pintype "passive"))
      (node (ref "J2") (pin "A9") (pinfunction "VBUS_A9") (pintype "passive"))
      (node (ref "J2") (pin "B9") (pinfunction "VBUS_B9") (pintype "passive"))
      (node (ref "J8") (pin "1") (pinfunction "VBUS_1") (pintype "passive"))
      (node (ref "J9") (pin "1") (pinfunction "VBUS_1") (pintype "passive"))
      (node (ref "P1") (pin "1") (pinfunction "1_1") (pintype "passive"))
      (node (ref "U2") (pin "3") (pinfunction "VIN_3") (pintype "passive"))
    )
    (net (code "126") (name "GND") (class "Default")
      (node (ref "C10") (pin "2") (pinfunction "2_2") (pintype "passive"))
      (node (ref "C11") (pin "1") (pinfunction "1_1") (pintype "passive"))
      (node (ref "C12") (pin "2") (pinfunction "2_2") (pintype "passive"))
      (node (ref "C13") (pin "2") (pinfunction "2_2") (pintype "passive"))
      (node (ref "C14") (pin "2") (pinfunction "2_2") (pintype "passive"))
      (node (ref "C15") (pin "2") (pinfunction "2_2") (pintype "passive"))
      (node (ref "C16") (pin "2") (pinfunction "2_2") (pintype "passive"))
      (node (ref "C17") (pin "2") (pinfunction "2_2") (pintype "passive"))
      (node (ref "C2") (pin "2") (pinfunction "2_2") (pintype "passive"))
      (node (ref "C3") (pin "2") (pinfunction "2_2") (pintype "passive"))
      (node (ref "C5") (pin "2") (pinfunction "2_2") (pintype "passive"))
      (node (ref "C6") (pin "1") (pinfunction "1_1") (pintype "passive"))
      (node (ref "C7") (pin "1") (pinfunction "1_1") (pintype "passive"))
      (node (ref "C9") (pin "2") (pinfunction "2_2") (pintype "passive"))
      (node (ref "J2") (pin "A12") (pinfunction "GND_A12") (pintype "passive"))
      (node (ref "J2") (pin "B12") (pinfunction "GND_B12") (pintype "passive"))
      (node (ref "J8") (pin "4") (pinfunction "GND_4") (pintype "passive"))
      (node (ref "J9") (pin "4") (pinfunction "GND_4") (pintype "passive"))
      (node (ref "J9") (pin "7") (pinfunction "GND_DRAIN_7") (pintype "passive"))
      (node (ref "P1") (pin "2") (pinfunction "2_2") (pintype "passive"))
      (node (ref "P2") (pin "2") (pinfunction "2_2") (pintype "passive"))
      (node (ref "P4") (pin "16") (pinfunction "16_16") (pintype "passive"))
      (node (ref "P4") (pin "22") (pinfunction "22_22") (pintype "passive"))
      (node (ref "P5") (pin "23") (pinfunction "23_23") (pintype "passive"))
      (node (ref "R1") (pin "1") (pinfunction "1_1") (pintype "passive"))
      (node (ref "S1") (pin "2") (pinfunction "2_2") (pintype "passive"))
      (node (ref "S1") (pin "3") (pinfunction "3_3") (pintype "passive"))
      (node (ref "U1") (pin "119") (pinfunction "GND_119") (pintype "passive"))
      (node (ref "U1") (pin "125") (pinfunction "GND_125") (pintype "passive"))
      (node (ref "U1") (pin "19") (pinfunction "GND_19") (pintype "passive"))
      (node (ref "U1") (pin "24") (pinfunction "GND_24") (pintype "passive"))
      (node (ref "U1") (pin "27") (pinfunction "GND_27") (pintype "passive"))
      (node (ref "U1") (pin "44") (pinfunction "GND_44") (pintype "passive"))
      (node (ref "U1") (pin "5") (pinfunction "GND_5") (pintype "passive"))
      (node (ref "U1") (pin "53") (pinfunction "GND_53") (pintype "passive"))
      (node (ref "U1") (pin "6") (pinfunction "GND_6") (pintype "passive"))
      (node (ref "U1") (pin "62") (pinfunction "GND_62") (pintype "passive"))
      (node (ref "U1") (pin "7") (pinfunction "GND_7") (pintype "passive"))
      (node (ref "U1") (pin "8") (pinfunction "GND_8") (pintype "passive"))
      (node (ref "U1") (pin "92") (pinfunction "GND_92") (pintype "passive"))
      (node (ref "U2") (pin "1") (pinfunction "GND_1") (pintype "passive"))
    )
    (net (code "127") (name "Net-(C11-Pad2)") (class "Default")
      (node (ref "C11") (pin "2") (pinfunction "2_2") (pintype "passive"))
      (node (ref "J7") (pin "9") (pinfunction "Shell_9") (pintype "passive"))
      (node (ref "R1") (pin "2") (pinfunction "2_2") (pintype "passive"))
    )
    (net (code "128") (name "Net-(C12-Pad1)") (class "Default")
      (node (ref "C12") (pin "1") (pinfunction "1_1") (pintype "passive"))
      (node (ref "R2") (pin "1") (pinfunction "1_1") (pintype "passive"))
    )
    (net (code "129") (name "Net-(C13-Pad1)") (class "Default")
      (node (ref "C13") (pin "1") (pinfunction "1_1") (pintype "passive"))
      (node (ref "U3") (pin "9") (pinfunction "9_9") (pintype "passive"))
    )
    (net (code "130") (name "Net-(C14-Pad1)") (class "Default")
      (node (ref "C14") (pin "1") (pinfunction "1_1") (pintype "passive"))
      (node (ref "U4") (pin "9") (pinfunction "9_9") (pintype "passive"))
    )
    (net (code "131") (name "Net-(C15-Pad1)") (class "Default")
      (node (ref "C15") (pin "1") (pinfunction "1_1") (pintype "passive"))
      (node (ref "U5") (pin "9") (pinfunction "9_9") (pintype "passive"))
    )
    (net (code "132") (name "Net-(C16-Pad1)") (class "Default")
      (node (ref "C16") (pin "1") (pinfunction "1_1") (pintype "passive"))
      (node (ref "U6") (pin "9") (pinfunction "9_9") (pintype "passive"))
    )
    (net (code "133") (name "Net-(C17-Pad1)") (class "Default")
      (node (ref "C17") (pin "1") (pinfunction "1_1") (pintype "passive"))
      (node (ref "U7") (pin "9") (pinfunction "9_9") (pintype "passive"))
    )
    (net (code "134") (name "Net-(J3-Pad1)") (class "Default")
      (node (ref "J3") (pin "1") (pinfunction "1_1") (pintype "passive"))
      (node (ref "U3") (pin "11") (pinfunction "11_11") (pintype "passive"))
    )
    (net (code "135") (name "Net-(J3-Pad2)") (class "Default")
      (node (ref "J3") (pin "2") (pinfunction "2_2") (pintype "passive"))
      (node (ref "U3") (pin "12") (pinfunction "12_12") (pintype "passive"))
    )
    (net (code "136") (name "Net-(J3-Pad3)") (class "Default")
      (node (ref "J3") (pin "3") (pinfunction "3_3") (pintype "passive"))
      (node (ref "U3") (pin "13") (pinfunction "13_13") (pintype "passive"))
    )
    (net (code "137") (name "Net-(J3-Pad4)") (class "Default")
      (node (ref "J3") (pin "4") (pinfunction "4_4") (pintype "passive"))
      (node (ref "U3") (pin "15") (pinfunction "15_15") (pintype "passive"))
    )
    (net (code "138") (name "Net-(J3-Pad5)") (class "Default")
      (node (ref "J3") (pin "5") (pinfunction "5_5") (pintype "passive"))
      (node (ref "U3") (pin "16") (pinfunction "16_16") (pintype "passive"))
    )
    (net (code "139") (name "Net-(J3-Pad6)") (class "Default")
      (node (ref "J3") (pin "6") (pinfunction "6_6") (pintype "passive"))
      (node (ref "U3") (pin "14") (pinfunction "14_14") (pintype "passive"))
    )
    (net (code "140") (name "Net-(J3-Pad7)") (class "Default")
      (node (ref "J3") (pin "7") (pinfunction "7_7") (pintype "passive"))
      (node (ref "U3") (pin "17") (pinfunction "17_17") (pintype "passive"))
    )
    (net (code "141") (name "Net-(J3-Pad8)") (class "Default")
      (node (ref "J3") (pin "8") (pinfunction "8_8") (pintype "passive"))
      (node (ref "U3") (pin "18") (pinfunction "18_18") (pintype "passive"))
    )
    (net (code "142") (name "Net-(J3-Shell-Pad10)") (class "Default")
      (node (ref "J3") (pin "10") (pinfunction "Shell_10") (pintype "passive"))
      (node (ref "J3") (pin "9") (pinfunction "Shell_9") (pintype "passive"))
      (node (ref "J4") (pin "10") (pinfunction "Shell_10") (pintype "passive"))
    )
    (net (code "143") (name "Net-(J4-Pad1)") (class "Default")
      (node (ref "J4") (pin "1") (pinfunction "1_1") (pintype "passive"))
      (node (ref "U4") (pin "11") (pinfunction "11_11") (pintype "passive"))
    )
    (net (code "144") (name "Net-(J4-Pad2)") (class "Default")
      (node (ref "J4") (pin "2") (pinfunction "2_2") (pintype "passive"))
      (node (ref "U4") (pin "12") (pinfunction "12_12") (pintype "passive"))
    )
    (net (code "145") (name "Net-(J4-Pad3)") (class "Default")
      (node (ref "J4") (pin "3") (pinfunction "3_3") (pintype "passive"))
      (node (ref "U4") (pin "13") (pinfunction "13_13") (pintype "passive"))
    )
    (net (code "146") (name "Net-(J4-Pad4)") (class "Default")
      (node (ref "J4") (pin "4") (pinfunction "4_4") (pintype "passive"))
      (node (ref "U4") (pin "15") (pinfunction "15_15") (pintype "passive"))
    )
    (net (code "147") (name "Net-(J4-Pad5)") (class "Default")
      (node (ref "J4") (pin "5") (pinfunction "5_5") (pintype "passive"))
      (node (ref "U4") (pin "16") (pinfunction "16_16") (pintype "passive"))
    )
    (net (code "148") (name "Net-(J4-Pad6)") (class "Default")
      (node (ref "J4") (pin "6") (pinfunction "6_6") (pintype "passive"))
      (node (ref "U4") (pin "14") (pinfunction "14_14") (pintype "passive"))
    )
    (net (code "149") (name "Net-(J4-Pad7)") (class "Default")
      (node (ref "J4") (pin "7") (pinfunction "7_7") (pintype "passive"))
      (node (ref "U4") (pin "17") (pinfunction "17_17") (pintype "passive"))
    )
    (net (code "150") (name "Net-(J4-Pad8)") (class "Default")
      (node (ref "J4") (pin "8") (pinfunction "8_8") (pintype "passive"))
      (node (ref "U4") (pin "18") (pinfunction "18_18") (pintype "passive"))
    )
    (net (code "151") (name "Net-(J4-Shell-Pad9)") (class "Default")
      (node (ref "J4") (pin "9") (pinfunction "Shell_9") (pintype "passive"))
      (node (ref "J5") (pin "10") (pinfunction "Shell_10") (pintype "passive"))
    )
    (net (code "152") (name "Net-(J5-Pad1)") (class "Default")
      (node (ref "J5") (pin "1") (pinfunction "1_1") (pintype "passive"))
      (node (ref "U5") (pin "11") (pinfunction "11_11") (pintype "passive"))
    )
    (net (code "153") (name "Net-(J5-Pad2)") (class "Default")
      (node (ref "J5") (pin "2") (pinfunction "2_2") (pintype "passive"))
      (node (ref "U5") (pin "12") (pinfunction "12_12") (pintype "passive"))
    )
    (net (code "154") (name "Net-(J5-Pad3)") (class "Default")
      (node (ref "J5") (pin "3") (pinfunction "3_3") (pintype "passive"))
      (node (ref "U5") (pin "13") (pinfunction "13_13") (pintype "passive"))
    )
    (net (code "155") (name "Net-(J5-Pad4)") (class "Default")
      (node (ref "J5") (pin "4") (pinfunction "4_4") (pintype "passive"))
      (node (ref "U5") (pin "15") (pinfunction "15_15") (pintype "passive"))
    )
    (net (code "156") (name "Net-(J5-Pad5)") (class "Default")
      (node (ref "J5") (pin "5") (pinfunction "5_5") (pintype "passive"))
      (node (ref "U5") (pin "16") (pinfunction "16_16") (pintype "passive"))
    )
    (net (code "157") (name "Net-(J5-Pad6)") (class "Default")
      (node (ref "J5") (pin "6") (pinfunction "6_6") (pintype "passive"))
      (node (ref "U5") (pin "14") (pinfunction "14_14") (pintype "passive"))
    )
    (net (code "158") (name "Net-(J5-Pad7)") (class "Default")
      (node (ref "J5") (pin "7") (pinfunction "7_7") (pintype "passive"))
      (node (ref "U5") (pin "17") (pinfunction "17_17") (pintype "passive"))
    )
    (net (code "159") (name "Net-(J5-Pad8)") (class "Default")
      (node (ref "J5") (pin "8") (pinfunction "8_8") (pintype "passive"))
      (node (ref "U5") (pin "18") (pinfunction "18_18") (pintype "passive"))
    )
    (net (code "160") (name "Net-(J5-Shell-Pad9)") (class "Default")
      (node (ref "J5") (pin "9") (pinfunction "Shell_9") (pintype "passive"))
      (node (ref "J6") (pin "10") (pinfunction "Shell_10") (pintype "passive"))
    )
    (net (code "161") (name "Net-(J6-Pad1)") (class "Default")
      (node (ref "J6") (pin "1") (pinfunction "1_1") (pintype "passive"))
      (node (ref "U6") (pin "11") (pinfunction "11_11") (pintype "passive"))
    )
    (net (code "162") (name "Net-(J6-Pad2)") (class "Default")
      (node (ref "J6") (pin "2") (pinfunction "2_2") (pintype "passive"))
      (node (ref "U6") (pin "12") (pinfunction "12_12") (pintype "passive"))
    )
    (net (code "163") (name "Net-(J6-Pad3)") (class "Default")
      (node (ref "J6") (pin "3") (pinfunction "3_3") (pintype "passive"))
      (node (ref "U6") (pin "13") (pinfunction "13_13") (pintype "passive"))
    )
    (net (code "164") (name "Net-(J6-Pad4)") (class "Default")
      (node (ref "J6") (pin "4") (pinfunction "4_4") (pintype "passive"))
      (node (ref "U6") (pin "15") (pinfunction "15_15") (pintype "passive"))
    )
    (net (code "165") (name "Net-(J6-Pad5)") (class "Default")
      (node (ref "J6") (pin "5") (pinfunction "5_5") (pintype "passive"))
      (node (ref "U6") (pin "16") (pinfunction "16_16") (pintype "passive"))
    )
    (net (code "166") (name "Net-(J6-Pad6)") (class "Default")
      (node (ref "J6") (pin "6") (pinfunction "6_6") (pintype "passive"))
      (node (ref "U6") (pin "14") (pinfunction "14_14") (pintype "passive"))
    )
    (net (code "167") (name "Net-(J6-Pad7)") (class "Default")
      (node (ref "J6") (pin "7") (pinfunction "7_7") (pintype "passive"))
      (node (ref "U6") (pin "17") (pinfunction "17_17") (pintype "passive"))
    )
    (net (code "168") (name "Net-(J6-Pad8)") (class "Default")
      (node (ref "J6") (pin "8") (pinfunction "8_8") (pintype "passive"))
      (node (ref "U6") (pin "18") (pinfunction "18_18") (pintype "passive"))
    )
    (net (code "169") (name "Net-(J6-Shell-Pad9)") (class "Default")
      (node (ref "J6") (pin "9") (pinfunction "Shell_9") (pintype "passive"))
      (node (ref "J7") (pin "10") (pinfunction "Shell_10") (pintype "passive"))
    )
    (net (code "170") (name "Net-(J7-Pad1)") (class "Default")
      (node (ref "J7") (pin "1") (pinfunction "1_1") (pintype "passive"))
      (node (ref "U7") (pin "11") (pinfunction "11_11") (pintype "passive"))
    )
    (net (code "171") (name "Net-(J7-Pad2)") (class "Default")
      (node (ref "J7") (pin "2") (pinfunction "2_2") (pintype "passive"))
      (node (ref "U7") (pin "12") (pinfunction "12_12") (pintype "passive"))
    )
    (net (code "172") (name "Net-(J7-Pad3)") (class "Default")
      (node (ref "J7") (pin "3") (pinfunction "3_3") (pintype "passive"))
      (node (ref "U7") (pin "13") (pinfunction "13_13") (pintype "passive"))
    )
    (net (code "173") (name "Net-(J7-Pad4)") (class "Default")
      (node (ref "J7") (pin "4") (pinfunction "4_4") (pintype "passive"))
      (node (ref "U7") (pin "15") (pinfunction "15_15") (pintype "passive"))
    )
    (net (code "174") (name "Net-(J7-Pad5)") (class "Default")
      (node (ref "J7") (pin "5") (pinfunction "5_5") (pintype "passive"))
      (node (ref "U7") (pin "16") (pinfunction "16_16") (pintype "passive"))
    )
    (net (code "175") (name "Net-(J7-Pad6)") (class "Default")
      (node (ref "J7") (pin "6") (pinfunction "6_6") (pintype "passive"))
      (node (ref "U7") (pin "14") (pinfunction "14_14") (pintype "passive"))
    )
    (net (code "176") (name "Net-(J7-Pad7)") (class "Default")
      (node (ref "J7") (pin "7") (pinfunction "7_7") (pintype "passive"))
      (node (ref "U7") (pin "17") (pinfunction "17_17") (pintype "passive"))
    )
    (net (code "177") (name "Net-(J7-Pad8)") (class "Default")
      (node (ref "J7") (pin "8") (pinfunction "8_8") (pintype "passive"))
      (node (ref "U7") (pin "18") (pinfunction "18_18") (pintype "passive"))
    )
    (net (code "178") (name "Net-(R2-Pad2)") (class "Default")
      (node (ref "R2") (pin "2") (pinfunction "2_2") (pintype "passive"))
      (node (ref "U3") (pin "10") (pinfunction "10_10") (pintype "passive"))
      (node (ref "U4") (pin "10") (pinfunction "10_10") (pintype "passive"))
      (node (ref "U5") (pin "10") (pinfunction "10_10") (pintype "passive"))
      (node (ref "U6") (pin "10") (pinfunction "10_10") (pintype "passive"))
      (node (ref "U7") (pin "10") (pinfunction "10_10") (pintype "passive"))
    )
    (net (code "179") (name "unconnected-(J2-CC1-PadA5)") (class "Default")
      (node (ref "J2") (pin "A5") (pinfunction "CC1_A5") (pintype "passive"))
    )
    (net (code "180") (name "unconnected-(J2-CC2-PadB5)") (class "Default")
      (node (ref "J2") (pin "B5") (pinfunction "CC2_B5") (pintype "passive"))
    )
    (net (code "181") (name "unconnected-(P4-Pad36)") (class "Default")
      (node (ref "P4") (pin "36") (pinfunction "36_36") (pintype "passive"))
    )
    (net (code "182") (name "unconnected-(P5-Pad1)") (class "Default")
      (node (ref "P5") (pin "1") (pinfunction "1_1") (pintype "passive"))
    )
  )
)
